# vga12-wing.net
KiCad netlist of a schematic drawn in Altium Designer
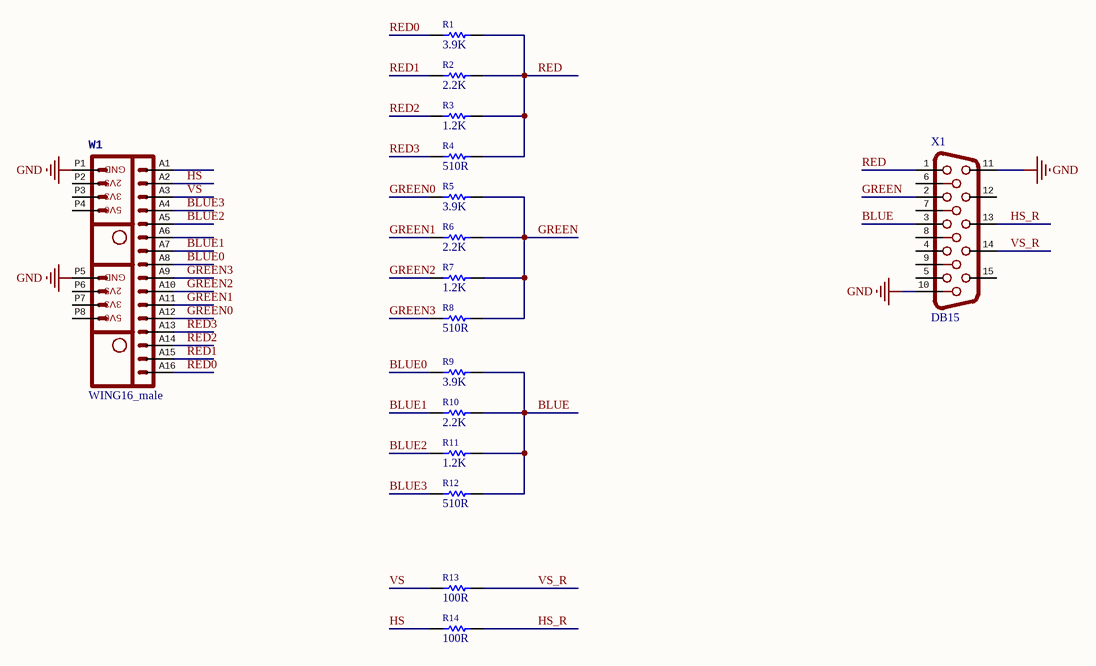
[diagram p0: vga12-wing.SchDoc]

(export (version "E")
  (design (tool "Eeschema 10.0.6"))
  (components
    (comp (ref "R1")
      (value "3.9K")
      (footprint "R0805_M")
      (description "Chip Resistor size 0805")
      (libsource (lib "MH - RCLDSX") (part "R0805"))
    )
    (comp (ref "R2")
      (value "2.2K")
      (footprint "R0805_M")
      (description "Chip Resistor size 0805")
      (libsource (lib "MH - RCLDSX") (part "R0805"))
    )
    (comp (ref "R3")
      (value "1.2K")
      (footprint "R0805_M")
      (description "Chip Resistor size 0805")
      (libsource (lib "MH - RCLDSX") (part "R0805"))
    )
    (comp (ref "R4")
      (value "510R")
      (footprint "R0805_M")
      (description "Chip Resistor size 0805")
      (libsource (lib "MH - RCLDSX") (part "R0805"))
    )
    (comp (ref "R5")
      (value "3.9K")
      (footprint "R0805_M")
      (description "Chip Resistor size 0805")
      (libsource (lib "MH - RCLDSX") (part "R0805"))
    )
    (comp (ref "R6")
      (value "2.2K")
      (footprint "R0805_M")
      (description "Chip Resistor size 0805")
      (libsource (lib "MH - RCLDSX") (part "R0805"))
    )
    (comp (ref "R7")
      (value "1.2K")
      (footprint "R0805_M")
      (description "Chip Resistor size 0805")
      (libsource (lib "MH - RCLDSX") (part "R0805"))
    )
    (comp (ref "R8")
      (value "510R")
      (footprint "R0805_M")
      (description "Chip Resistor size 0805")
      (libsource (lib "MH - RCLDSX") (part "R0805"))
    )
    (comp (ref "R9")
      (value "3.9K")
      (footprint "R0805_M")
      (description "Chip Resistor size 0805")
      (libsource (lib "MH - RCLDSX") (part "R0805"))
    )
    (comp (ref "R10")
      (value "2.2K")
      (footprint "R0805_M")
      (description "Chip Resistor size 0805")
      (libsource (lib "MH - RCLDSX") (part "R0805"))
    )
    (comp (ref "R11")
      (value "1.2K")
      (footprint "R0805_M")
      (description "Chip Resistor size 0805")
      (libsource (lib "MH - RCLDSX") (part "R0805"))
    )
    (comp (ref "R12")
      (value "510R")
      (footprint "R0805_M")
      (description "Chip Resistor size 0805")
      (libsource (lib "MH - RCLDSX") (part "R0805"))
    )
    (comp (ref "R13")
      (value "100R")
      (footprint "R0805_M")
      (description "Chip Resistor size 0805")
      (libsource (lib "MH - RCLDSX") (part "R0805"))
    )
    (comp (ref "R14")
      (value "100R")
      (footprint "R0805_M")
      (description "Chip Resistor size 0805")
      (libsource (lib "MH - RCLDSX") (part "R0805"))
    )
    (comp (ref "W1")
      (value "WING16_male")
      (footprint "WINGSIDE_16BIT - male")
      (description "Papilio Wing16")
      (libsource (lib "Papilio") (part "WING16_male"))
    )
    (comp (ref "X1")
      (value "DB15")
      (footprint "DB15_Female_Right_VGA")
      (description "DB15 Female Right Angle VGA Connector")
      (libsource (lib "MH - Connectors") (part "DB15_FEMALE_RIGHT_VGA"))
    )
  )
  (nets
    (net (code "1") (name "/BLUE") (class "Default")
      (node (ref "R10") (pin "1") (pinfunction "1_1") (pintype "passive"))
      (node (ref "R11") (pin "1") (pinfunction "1_1") (pintype "passive"))
      (node (ref "R12") (pin "1") (pinfunction "1_1") (pintype "passive"))
      (node (ref "R9") (pin "1") (pinfunction "1_1") (pintype "passive"))
      (node (ref "X1") (pin "3") (pinfunction "3_3") (pintype "passive"))
    )
    (net (code "2") (name "/BLUE0") (class "Default")
      (node (ref "R9") (pin "2") (pinfunction "2_2") (pintype "passive"))
      (node (ref "W1") (pin "A8") (pinfunction "A8_A8") (pintype "passive"))
    )
    (net (code "3") (name "/BLUE1") (class "Default")
      (node (ref "R10") (pin "2") (pinfunction "2_2") (pintype "passive"))
      (node (ref "W1") (pin "A7") (pinfunction "A7_A7") (pintype "passive"))
    )
    (net (code "4") (name "/BLUE2") (class "Default")
      (node (ref "R11") (pin "2") (pinfunction "2_2") (pintype "passive"))
      (node (ref "W1") (pin "A5") (pinfunction "A5_A5") (pintype "passive"))
    )
    (net (code "5") (name "/BLUE3") (class "Default")
      (node (ref "R12") (pin "2") (pinfunction "2_2") (pintype "passive"))
      (node (ref "W1") (pin "A4") (pinfunction "A4_A4") (pintype "passive"))
    )
    (net (code "6") (name "/GREEN") (class "Default")
      (node (ref "R5") (pin "1") (pinfunction "1_1") (pintype "passive"))
      (node (ref "R6") (pin "1") (pinfunction "1_1") (pintype "passive"))
      (node (ref "R7") (pin "1") (pinfunction "1_1") (pintype "passive"))
      (node (ref "R8") (pin "1") (pinfunction "1_1") (pintype "passive"))
      (node (ref "X1") (pin "2") (pinfunction "2_2") (pintype "passive"))
    )
    (net (code "7") (name "/GREEN0") (class "Default")
      (node (ref "R5") (pin "2") (pinfunction "2_2") (pintype "passive"))
      (node (ref "W1") (pin "A12") (pinfunction "A12_A12") (pintype "passive"))
    )
    (net (code "8") (name "/GREEN1") (class "Default")
      (node (ref "R6") (pin "2") (pinfunction "2_2") (pintype "passive"))
      (node (ref "W1") (pin "A11") (pinfunction "A11_A11") (pintype "passive"))
    )
    (net (code "9") (name "/GREEN2") (class "Default")
      (node (ref "R7") (pin "2") (pinfunction "2_2") (pintype "passive"))
      (node (ref "W1") (pin "A10") (pinfunction "A10_A10") (pintype "passive"))
    )
    (net (code "10") (name "/GREEN3") (class "Default")
      (node (ref "R8") (pin "2") (pinfunction "2_2") (pintype "passive"))
      (node (ref "W1") (pin "A9") (pinfunction "A9_A9") (pintype "passive"))
    )
    (net (code "11") (name "/HS") (class "Default")
      (node (ref "R14") (pin "2") (pinfunction "2_2") (pintype "passive"))
      (node (ref "W1") (pin "A2") (pinfunction "A2_A2") (pintype "passive"))
    )
    (net (code "12") (name "/HS_R") (class "Default")
      (node (ref "R14") (pin "1") (pinfunction "1_1") (pintype "passive"))
      (node (ref "X1") (pin "13") (pinfunction "13_13") (pintype "passive"))
    )
    (net (code "13") (name "/RED") (class "Default")
      (node (ref "R1") (pin "1") (pinfunction "1_1") (pintype "passive"))
      (node (ref "R2") (pin "1") (pinfunction "1_1") (pintype "passive"))
      (node (ref "R3") (pin "1") (pinfunction "1_1") (pintype "passive"))
      (node (ref "R4") (pin "1") (pinfunction "1_1") (pintype "passive"))
      (node (ref "X1") (pin "1") (pinfunction "1_1") (pintype "passive"))
    )
    (net (code "14") (name "/RED0") (class "Default")
      (node (ref "R1") (pin "2") (pinfunction "2_2") (pintype "passive"))
      (node (ref "W1") (pin "A16") (pinfunction "A16_A16") (pintype "passive"))
    )
    (net (code "15") (name "/RED1") (class "Default")
      (node (ref "R2") (pin "2") (pinfunction "2_2") (pintype "passive"))
      (node (ref "W1") (pin "A15") (pinfunction "A15_A15") (pintype "passive"))
    )
    (net (code "16") (name "/RED2") (class "Default")
      (node (ref "R3") (pin "2") (pinfunction "2_2") (pintype "passive"))
      (node (ref "W1") (pin "A14") (pinfunction "A14_A14") (pintype "passive"))
    )
    (net (code "17") (name "/RED3") (class "Default")
      (node (ref "R4") (pin "2") (pinfunction "2_2") (pintype "passive"))
      (node (ref "W1") (pin "A13") (pinfunction "A13_A13") (pintype "passive"))
    )
    (net (code "18") (name "/VS") (class "Default")
      (node (ref "R13") (pin "2") (pinfunction "2_2") (pintype "passive"))
      (node (ref "W1") (pin "A3") (pinfunction "A3_A3") (pintype "passive"))
    )
    (net (code "19") (name "/VS_R") (class "Default")
      (node (ref "R13") (pin "1") (pinfunction "1_1") (pintype "passive"))
      (node (ref "X1") (pin "14") (pinfunction "14_14") (pintype "passive"))
    )
    (net (code "20") (name "GND") (class "Default")
      (node (ref "W1") (pin "P1") (pinfunction "GND_P1") (pintype "passive"))
      (node (ref "W1") (pin "P5") (pinfunction "GND_P5") (pintype "passive"))
      (node (ref "X1") (pin "10") (pinfunction "10_10") (pintype "passive"))
      (node (ref "X1") (pin "11") (pinfunction "11_11") (pintype "passive"))
    )
    (net (code "21") (name "unconnected-(W1-2V2-PadP2)") (class "Default")
      (node (ref "W1") (pin "P2") (pinfunction "2V2_P2") (pintype "passive"))
    )
    (net (code "22") (name "unconnected-(W1-2V5-PadP6)") (class "Default")
      (node (ref "W1") (pin "P6") (pinfunction "2V5_P6") (pintype "passive"))
    )
    (net (code "23") (name "unconnected-(W1-3V3-PadP3)") (class "Default")
      (node (ref "W1") (pin "P3") (pinfunction "3V3_P3") (pintype "passive"))
    )
    (net (code "24") (name "unconnected-(W1-3V3-PadP7)") (class "Default")
      (node (ref "W1") (pin "P7") (pinfunction "3V3_P7") (pintype "passive"))
    )
    (net (code "25") (name "unconnected-(W1-5V-PadP4)") (class "Default")
      (node (ref "W1") (pin "P4") (pinfunction "5V_P4") (pintype "passive"))
    )
    (net (code "26") (name "unconnected-(W1-5V-PadP8)") (class "Default")
      (node (ref "W1") (pin "P8") (pinfunction "5V_P8") (pintype "passive"))
    )
    (net (code "27") (name "unconnected-(W1-PadA1)") (class "Default")
      (node (ref "W1") (pin "A1") (pinfunction "A1_A1") (pintype "passive"))
    )
    (net (code "28") (name "unconnected-(W1-PadA6)") (class "Default")
      (node (ref "W1") (pin "A6") (pinfunction "A6_A6") (pintype "passive"))
    )
    (net (code "29") (name "unconnected-(X1-Pad4)") (class "Default")
      (node (ref "X1") (pin "4") (pinfunction "4_4") (pintype "passive"))
    )
    (net (code "30") (name "unconnected-(X1-Pad5)") (class "Default")
      (node (ref "X1") (pin "5") (pinfunction "5_5") (pintype "passive"))
    )
    (net (code "31") (name "unconnected-(X1-Pad6)") (class "Default")
      (node (ref "X1") (pin "6") (pinfunction "6_6") (pintype "passive"))
    )
    (net (code "32") (name "unconnected-(X1-Pad7)") (class "Default")
      (node (ref "X1") (pin "7") (pinfunction "7_7") (pintype "passive"))
    )
    (net (code "33") (name "unconnected-(X1-Pad8)") (class "Default")
      (node (ref "X1") (pin "8") (pinfunction "8_8") (pintype "passive"))
    )
    (net (code "34") (name "unconnected-(X1-Pad9)") (class "Default")
      (node (ref "X1") (pin "9") (pinfunction "9_9") (pintype "passive"))
    )
    (net (code "35") (name "unconnected-(X1-Pad12)") (class "Default")
      (node (ref "X1") (pin "12") (pinfunction "12_12") (pintype "passive"))
    )
    (net (code "36") (name "unconnected-(X1-Pad15)") (class "Default")
      (node (ref "X1") (pin "15") (pinfunction "15_15") (pintype "passive"))
    )
  )
)
